# bias.net
KiCad netlist of a schematic drawn in Altium Designer
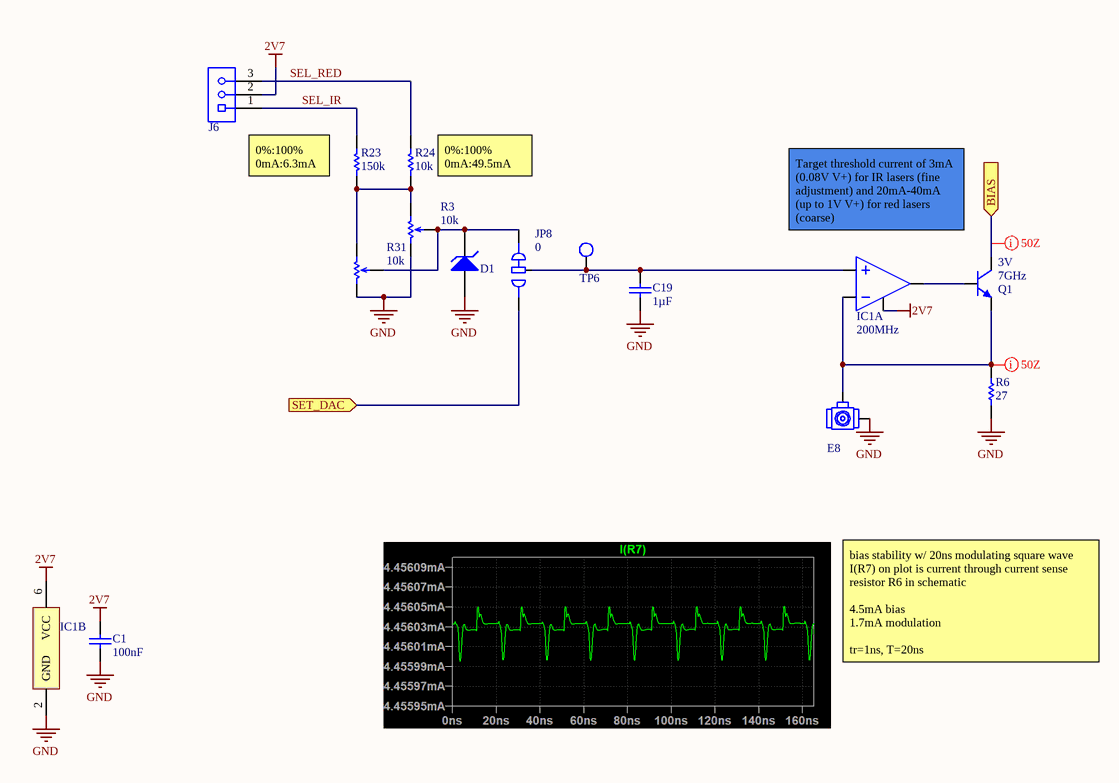
[diagram p0: bias.SchDoc]

(export (version "E")
  (design (tool "Eeschema 10.0.6"))
  (components
    (comp (ref "C1")
      (value "100nF")
      (footprint "CAPC1005X06N")
      (fields (field (name "TOLERANCE") "10%") (field (name "Comment") "CL05B104KB54PNC"))
      (libsource (lib "UWA Aerospace") (part "Capacitor - Non-polar"))
    )
    (comp (ref "C19")
      (value "1µF")
      (footprint "CAPC1005X06N")
      (fields (field (name "TOLERANCE") "10%") (field (name "Comment") "CL05A105KA5NQNC"))
      (libsource (lib "UWA Aerospace") (part "Capacitor - Non-polar"))
    )
    (comp (ref "D1")
      (value "H5VU10U")
      (footprint "DFN60P100X45-2L")
      (description "5A 55W 16V 9V Unidirectional 5V DFN1006-2L  ESD and Surge Protection (TVS/ESD) ROHS")
      (libsource (lib "UWA Aerospace") (part "Diode - Zener"))
    )
    (comp (ref "E8")
      (value "U.FL-R-SMT-1(01)")
      (footprint "HRS-U.FL-R-SMT-3_V 4_LAYER_KO")
      (description "Rf Connectors / Coaxial Connectors SMT Ml Rec Au 50 Ohm W/anti Sldr Wicking UFL")
      (fields (field (name "SOURCE") "UWAA_Stock"))
      (libsource (lib "UWA Aerospace") (part "U.FL Connector"))
    )
    (comp (ref "IC1")
      (value "OPA355NA/3K")
      (footprint "DBV0006A_SOT-23-6_TI__SOT95P280X145-6L")
      (description "Operational Amplifier, 1 Func, 9000uV Offset-Max, 100MHz Band Width, CMOS, PDSO6")
      (fields
        (field (name "GAIN BANDWIDTH PRODUCT") "200MHz")
        (field (name "SOURCE") "JLCPCB(Extended,Economic_PCBA)")
      )
      (libsource (lib "") (part "Amplifier - Operational w/ EN_1"))
    )
    (comp (ref "J6")
      (value "10129378-903001BLF")
      (footprint "10129378-903001BLF-Footprint-1")
      (description "Conn Unshrouded Header HDR 3 POS 2.54mm Solder ST Thru-Hole Poly Bag")
      (fields (field (name "SOURCE") "Aliexpress"))
      (libsource (lib "UWA Aerospace") (part "10129378-903001BLF"))
    )
    (comp (ref "JP8")
      (value "0")
      (footprint "RESC1005X04N TWO STATE")
      (description "JUMPER-0402 TWO STATE Fixed Resistor, Metal Glaze/thick Film, 0.1W, 0ohm, Surface Mount, 0402")
      (fields (field (name "TOLERANCE") "1%") (field (name "Comment") "JUMPER-0402 TWO STATE"))
      (libsource (lib "UWA Aerospace") (part "Jumper - Two state"))
    )
    (comp (ref "Q1")
      (value "2SC3356")
      (footprint "SOT-23_hongjiacheng__SOT95P240X115-3L")
      (description "RF Small Signal Bipolar Transistor, 0.1A I(C), 1-Element, Ultra High Frequency Band, Silicon, NPN")
      (fields (field (name "FREQUENCY") "7GHz") (field (name "EMITTER BASE VOLTAGE (VEBO)") "3V"))
      (libsource (lib "UWA Aerospace") (part "Transistor - BJT NPN"))
    )
    (comp (ref "R3")
      (value "10k")
      (footprint "BOUR-TC33X-2_V")
      (description "Res Trimmer 10K Ohm 25% 1/10W 1(Elec)/1(Mech)Turn (3 X 3.8mm) Foot Print SMD Embossed T/R")
      (fields (field (name "TOLERANCE") "25%") (field (name "Comment") "TC33X-2-103E"))
      (libsource (lib "UWA Aerospace") (part "Resistor - Adjustable"))
    )
    (comp (ref "R6")
      (value "27")
      (footprint "RESC1608X05N")
      (description "Res Thick Film 0603 27 Ohm 5% 1/10W +/-200ppm/ßC Molded SMD Punched Carrier T/R")
      (fields (field (name "TOLERANCE") "5%") (field (name "Comment") "ERJ-3GEYJ270V"))
      (libsource (lib "UWA Aerospace") (part "Resistor"))
    )
    (comp (ref "R23")
      (value "150k")
      (footprint "RESC2012X05N")
      (description "Thick Film Resistors - SMD RMC 0805 1/8W 1% T/R-5000")
      (fields (field (name "TOLERANCE") "1%") (field (name "Comment") "0805W8F1503T5E"))
      (libsource (lib "UWA Aerospace") (part "Resistor"))
    )
    (comp (ref "R24")
      (value "10k")
      (footprint "RESC2012X05N")
      (description "Res Thick Film 0805 10K Ohm 1% 0.125W(1/8W) ±100ppm/C Pad SMD T/R")
      (fields (field (name "TOLERANCE") "1%") (field (name "Comment") "0805W8F1002T5E"))
      (libsource (lib "UWA Aerospace") (part "Resistor"))
    )
    (comp (ref "R31")
      (value "10k")
      (footprint "POT_RK0971-L-15KC_N-1")
      (description "Potentiometer, 0.05W, 10000ohm, 10V, 20% +/-Tol, 1 Turn(s)")
      (fields
        (field (name "TOLERANCE") "20%")
        (field (name "Comment") "RK0971114D0B")
        (field (name "SOURCE") "Aliexpress")
      )
      (libsource (lib "UWA Aerospace") (part "Resistor - Adjustable"))
    )
    (comp (ref "TP6")
      (value "Test Point 5001")
      (footprint "FP-5001-MFG")
      (fields (field (name "SOURCE") "UWAA_Stock"))
      (libsource (lib "UWA Aerospace") (part "Test Point"))
    )
  )
  (nets
    (net (code "1") (name "/BIAS") (class "Default")
      (node (ref "Q1") (pin "1") (pinfunction "C_1") (pintype "passive"))
    )
    (net (code "2") (name "/SEL_IR") (class "Default")
      (node (ref "J6") (pin "1") (pinfunction "1_1") (pintype "passive"))
      (node (ref "R23") (pin "2") (pinfunction "2_2") (pintype "passive"))
    )
    (net (code "3") (name "/SEL_RED") (class "Default")
      (node (ref "J6") (pin "3") (pinfunction "3_3") (pintype "passive"))
      (node (ref "R24") (pin "2") (pinfunction "2_2") (pintype "passive"))
    )
    (net (code "4") (name "/SET_DAC") (class "Default")
      (node (ref "JP8") (pin "1") (pinfunction "1_1") (pintype "passive"))
    )
    (net (code "5") (name "2V7") (class "Default")
      (node (ref "C1") (pin "2") (pinfunction "2_2") (pintype "passive"))
      (node (ref "IC1") (pin "5") (pinfunction "ENABLE_5") (pintype "passive"))
      (node (ref "IC1") (pin "6") (pinfunction "VCC_6") (pintype "passive"))
      (node (ref "J6") (pin "2") (pinfunction "2_2") (pintype "passive"))
    )
    (net (code "6") (name "GND") (class "Default")
      (node (ref "C1") (pin "1") (pinfunction "1_1") (pintype "passive"))
      (node (ref "C19") (pin "1") (pinfunction "1_1") (pintype "passive"))
      (node (ref "D1") (pin "2") (pinfunction "A_2") (pintype "passive"))
      (node (ref "E8") (pin "2") (pinfunction "GND_2") (pintype "passive"))
      (node (ref "IC1") (pin "2") (pinfunction "GND_2") (pintype "passive"))
      (node (ref "R3") (pin "1") (pinfunction "CCW_1") (pintype "passive"))
      (node (ref "R31") (pin "1") (pinfunction "CCW_1") (pintype "passive"))
      (node (ref "R6") (pin "1") (pinfunction "1_1") (pintype "passive"))
    )
    (net (code "7") (name "Net-(D1-K)") (class "Default")
      (node (ref "D1") (pin "1") (pinfunction "K_1") (pintype "passive"))
      (node (ref "JP8") (pin "2") (pinfunction "2_2") (pintype "passive"))
      (node (ref "R3") (pin "2") (pinfunction "W_2") (pintype "passive"))
      (node (ref "R31") (pin "2") (pinfunction "W_2") (pintype "passive"))
    )
    (net (code "8") (name "Net-(E8-SIG)") (class "Default")
      (node (ref "E8") (pin "1") (pinfunction "SIG_1") (pintype "passive"))
      (node (ref "IC1") (pin "4") (pinfunction "VIN-_4") (pintype "passive"))
      (node (ref "Q1") (pin "3") (pinfunction "E_3") (pintype "passive"))
      (node (ref "R6") (pin "2") (pinfunction "2_2") (pintype "passive"))
    )
    (net (code "9") (name "Net-(IC1A-VIN+)") (class "Default")
      (node (ref "C19") (pin "2") (pinfunction "2_2") (pintype "passive"))
      (node (ref "IC1") (pin "3") (pinfunction "VIN+_3") (pintype "passive"))
      (node (ref "JP8") (pin "3") (pinfunction "COM_3") (pintype "passive"))
      (node (ref "TP6") (pin "1") (pinfunction "1_1") (pintype "passive"))
    )
    (net (code "10") (name "Net-(IC1A-VOUT)") (class "Default")
      (node (ref "IC1") (pin "1") (pinfunction "VOUT_1") (pintype "passive"))
      (node (ref "Q1") (pin "2") (pinfunction "B_2") (pintype "passive"))
    )
    (net (code "11") (name "Net-(R3-CW)") (class "Default")
      (node (ref "R23") (pin "1") (pinfunction "1_1") (pintype "passive"))
      (node (ref "R24") (pin "1") (pinfunction "1_1") (pintype "passive"))
      (node (ref "R3") (pin "3") (pinfunction "CW_3") (pintype "passive"))
      (node (ref "R31") (pin "3") (pinfunction "CW_3") (pintype "passive"))
    )
  )
)
